# Main_LEDs.net
KiCad netlist of a schematic drawn in Altium Designer
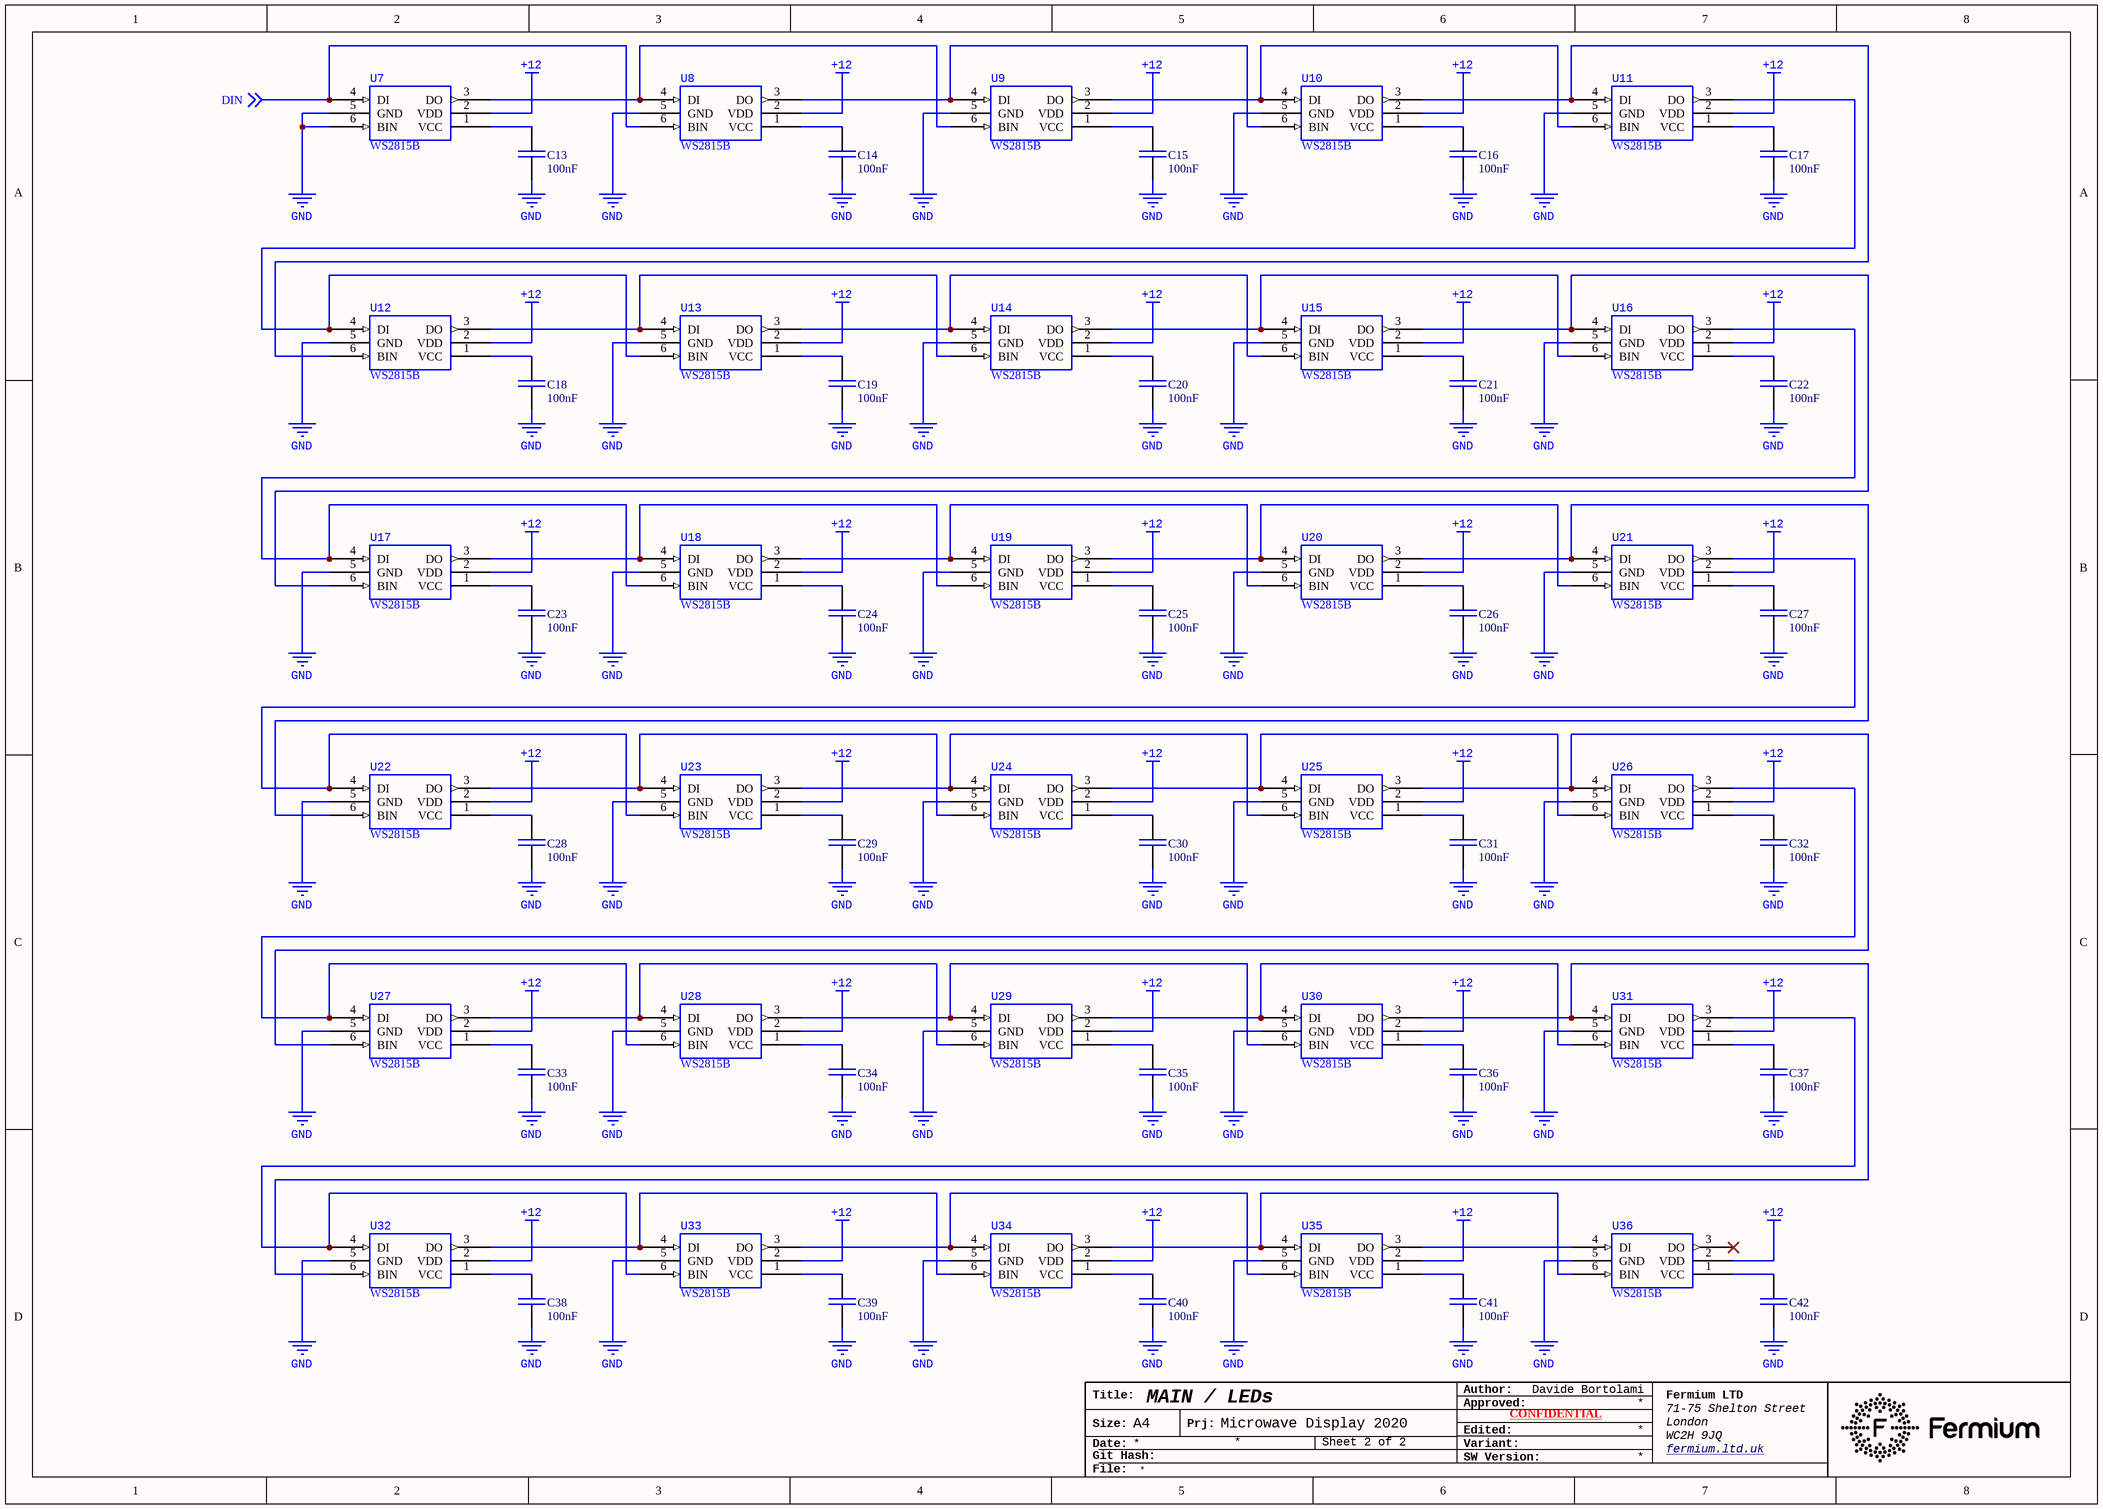
[diagram p0: Main_LEDs.SchDoc]

(export (version "E")
  (design (tool "Eeschema 10.0.6"))
  (components
    (comp (ref "C13")
      (value "100nF")
      (footprint "CAP 0603_1608")
      (description "CAP SMD MLCC 100nF 25V 0603 X7R")
      (fields (field (name "PART NUMBER") "02841f84-ac15-41b5-9e17-915f8f067828"))
      (libsource (lib "frmdblib") (part "GENERIC_C"))
    )
    (comp (ref "C14")
      (value "100nF")
      (footprint "CAP 0603_1608")
      (description "CAP SMD MLCC 100nF 25V 0603 X7R")
      (fields (field (name "PART NUMBER") "02841f84-ac15-41b5-9e17-915f8f067828"))
      (libsource (lib "frmdblib") (part "GENERIC_C"))
    )
    (comp (ref "C15")
      (value "100nF")
      (footprint "CAP 0603_1608")
      (description "CAP SMD MLCC 100nF 25V 0603 X7R")
      (fields (field (name "PART NUMBER") "02841f84-ac15-41b5-9e17-915f8f067828"))
      (libsource (lib "frmdblib") (part "GENERIC_C"))
    )
    (comp (ref "C16")
      (value "100nF")
      (footprint "CAP 0603_1608")
      (description "CAP SMD MLCC 100nF 25V 0603 X7R")
      (fields (field (name "PART NUMBER") "02841f84-ac15-41b5-9e17-915f8f067828"))
      (libsource (lib "frmdblib") (part "GENERIC_C"))
    )
    (comp (ref "C17")
      (value "100nF")
      (footprint "CAP 0603_1608")
      (description "CAP SMD MLCC 100nF 25V 0603 X7R")
      (fields (field (name "PART NUMBER") "02841f84-ac15-41b5-9e17-915f8f067828"))
      (libsource (lib "frmdblib") (part "GENERIC_C"))
    )
    (comp (ref "C18")
      (value "100nF")
      (footprint "CAP 0603_1608")
      (description "CAP SMD MLCC 100nF 25V 0603 X7R")
      (fields (field (name "PART NUMBER") "02841f84-ac15-41b5-9e17-915f8f067828"))
      (libsource (lib "frmdblib") (part "GENERIC_C"))
    )
    (comp (ref "C19")
      (value "100nF")
      (footprint "CAP 0603_1608")
      (description "CAP SMD MLCC 100nF 25V 0603 X7R")
      (fields (field (name "PART NUMBER") "02841f84-ac15-41b5-9e17-915f8f067828"))
      (libsource (lib "frmdblib") (part "GENERIC_C"))
    )
    (comp (ref "C20")
      (value "100nF")
      (footprint "CAP 0603_1608")
      (description "CAP SMD MLCC 100nF 25V 0603 X7R")
      (fields (field (name "PART NUMBER") "02841f84-ac15-41b5-9e17-915f8f067828"))
      (libsource (lib "frmdblib") (part "GENERIC_C"))
    )
    (comp (ref "C21")
      (value "100nF")
      (footprint "CAP 0603_1608")
      (description "CAP SMD MLCC 100nF 25V 0603 X7R")
      (fields (field (name "PART NUMBER") "02841f84-ac15-41b5-9e17-915f8f067828"))
      (libsource (lib "frmdblib") (part "GENERIC_C"))
    )
    (comp (ref "C22")
      (value "100nF")
      (footprint "CAP 0603_1608")
      (description "CAP SMD MLCC 100nF 25V 0603 X7R")
      (fields (field (name "PART NUMBER") "02841f84-ac15-41b5-9e17-915f8f067828"))
      (libsource (lib "frmdblib") (part "GENERIC_C"))
    )
    (comp (ref "C23")
      (value "100nF")
      (footprint "CAP 0603_1608")
      (description "CAP SMD MLCC 100nF 25V 0603 X7R")
      (fields (field (name "PART NUMBER") "02841f84-ac15-41b5-9e17-915f8f067828"))
      (libsource (lib "frmdblib") (part "GENERIC_C"))
    )
    (comp (ref "C24")
      (value "100nF")
      (footprint "CAP 0603_1608")
      (description "CAP SMD MLCC 100nF 25V 0603 X7R")
      (fields (field (name "PART NUMBER") "02841f84-ac15-41b5-9e17-915f8f067828"))
      (libsource (lib "frmdblib") (part "GENERIC_C"))
    )
    (comp (ref "C25")
      (value "100nF")
      (footprint "CAP 0603_1608")
      (description "CAP SMD MLCC 100nF 25V 0603 X7R")
      (fields (field (name "PART NUMBER") "02841f84-ac15-41b5-9e17-915f8f067828"))
      (libsource (lib "frmdblib") (part "GENERIC_C"))
    )
    (comp (ref "C26")
      (value "100nF")
      (footprint "CAP 0603_1608")
      (description "CAP SMD MLCC 100nF 25V 0603 X7R")
      (fields (field (name "PART NUMBER") "02841f84-ac15-41b5-9e17-915f8f067828"))
      (libsource (lib "frmdblib") (part "GENERIC_C"))
    )
    (comp (ref "C27")
      (value "100nF")
      (footprint "CAP 0603_1608")
      (description "CAP SMD MLCC 100nF 25V 0603 X7R")
      (fields (field (name "PART NUMBER") "02841f84-ac15-41b5-9e17-915f8f067828"))
      (libsource (lib "frmdblib") (part "GENERIC_C"))
    )
    (comp (ref "C28")
      (value "100nF")
      (footprint "CAP 0603_1608")
      (description "CAP SMD MLCC 100nF 25V 0603 X7R")
      (fields (field (name "PART NUMBER") "02841f84-ac15-41b5-9e17-915f8f067828"))
      (libsource (lib "frmdblib") (part "GENERIC_C"))
    )
    (comp (ref "C29")
      (value "100nF")
      (footprint "CAP 0603_1608")
      (description "CAP SMD MLCC 100nF 25V 0603 X7R")
      (fields (field (name "PART NUMBER") "02841f84-ac15-41b5-9e17-915f8f067828"))
      (libsource (lib "frmdblib") (part "GENERIC_C"))
    )
    (comp (ref "C30")
      (value "100nF")
      (footprint "CAP 0603_1608")
      (description "CAP SMD MLCC 100nF 25V 0603 X7R")
      (fields (field (name "PART NUMBER") "02841f84-ac15-41b5-9e17-915f8f067828"))
      (libsource (lib "frmdblib") (part "GENERIC_C"))
    )
    (comp (ref "C31")
      (value "100nF")
      (footprint "CAP 0603_1608")
      (description "CAP SMD MLCC 100nF 25V 0603 X7R")
      (fields (field (name "PART NUMBER") "02841f84-ac15-41b5-9e17-915f8f067828"))
      (libsource (lib "frmdblib") (part "GENERIC_C"))
    )
    (comp (ref "C32")
      (value "100nF")
      (footprint "CAP 0603_1608")
      (description "CAP SMD MLCC 100nF 25V 0603 X7R")
      (fields (field (name "PART NUMBER") "02841f84-ac15-41b5-9e17-915f8f067828"))
      (libsource (lib "frmdblib") (part "GENERIC_C"))
    )
    (comp (ref "C33")
      (value "100nF")
      (footprint "CAP 0603_1608")
      (description "CAP SMD MLCC 100nF 25V 0603 X7R")
      (fields (field (name "PART NUMBER") "02841f84-ac15-41b5-9e17-915f8f067828"))
      (libsource (lib "frmdblib") (part "GENERIC_C"))
    )
    (comp (ref "C34")
      (value "100nF")
      (footprint "CAP 0603_1608")
      (description "CAP SMD MLCC 100nF 25V 0603 X7R")
      (fields (field (name "PART NUMBER") "02841f84-ac15-41b5-9e17-915f8f067828"))
      (libsource (lib "frmdblib") (part "GENERIC_C"))
    )
    (comp (ref "C35")
      (value "100nF")
      (footprint "CAP 0603_1608")
      (description "CAP SMD MLCC 100nF 25V 0603 X7R")
      (fields (field (name "PART NUMBER") "02841f84-ac15-41b5-9e17-915f8f067828"))
      (libsource (lib "frmdblib") (part "GENERIC_C"))
    )
    (comp (ref "C36")
      (value "100nF")
      (footprint "CAP 0603_1608")
      (description "CAP SMD MLCC 100nF 25V 0603 X7R")
      (fields (field (name "PART NUMBER") "02841f84-ac15-41b5-9e17-915f8f067828"))
      (libsource (lib "frmdblib") (part "GENERIC_C"))
    )
    (comp (ref "C37")
      (value "100nF")
      (footprint "CAP 0603_1608")
      (description "CAP SMD MLCC 100nF 25V 0603 X7R")
      (fields (field (name "PART NUMBER") "02841f84-ac15-41b5-9e17-915f8f067828"))
      (libsource (lib "frmdblib") (part "GENERIC_C"))
    )
    (comp (ref "C38")
      (value "100nF")
      (footprint "CAP 0603_1608")
      (description "CAP SMD MLCC 100nF 25V 0603 X7R")
      (fields (field (name "PART NUMBER") "02841f84-ac15-41b5-9e17-915f8f067828"))
      (libsource (lib "frmdblib") (part "GENERIC_C"))
    )
    (comp (ref "C39")
      (value "100nF")
      (footprint "CAP 0603_1608")
      (description "CAP SMD MLCC 100nF 25V 0603 X7R")
      (fields (field (name "PART NUMBER") "02841f84-ac15-41b5-9e17-915f8f067828"))
      (libsource (lib "frmdblib") (part "GENERIC_C"))
    )
    (comp (ref "C40")
      (value "100nF")
      (footprint "CAP 0603_1608")
      (description "CAP SMD MLCC 100nF 25V 0603 X7R")
      (fields (field (name "PART NUMBER") "02841f84-ac15-41b5-9e17-915f8f067828"))
      (libsource (lib "frmdblib") (part "GENERIC_C"))
    )
    (comp (ref "C41")
      (value "100nF")
      (footprint "CAP 0603_1608")
      (description "CAP SMD MLCC 100nF 25V 0603 X7R")
      (fields (field (name "PART NUMBER") "02841f84-ac15-41b5-9e17-915f8f067828"))
      (libsource (lib "frmdblib") (part "GENERIC_C"))
    )
    (comp (ref "C42")
      (value "100nF")
      (footprint "CAP 0603_1608")
      (description "CAP SMD MLCC 100nF 25V 0603 X7R")
      (fields (field (name "PART NUMBER") "02841f84-ac15-41b5-9e17-915f8f067828"))
      (libsource (lib "frmdblib") (part "GENERIC_C"))
    )
    (comp (ref "U7")
      (value "WS2815B")
      (footprint "C2100EF9-5A1B-4012-AEAB-289AE8E97B6B")
      (description "IC SMD LED RGB DIGITAL 12V WS2815B")
      (fields (field (name "PART NUMBER") "6f697cdb-93d0-46fc-8e29-f2cd6d395cf4"))
      (libsource (lib "frmdblib") (part "2030838a-96a2-4aaf-b84b-11e32876a490"))
    )
    (comp (ref "U8")
      (value "WS2815B")
      (footprint "C2100EF9-5A1B-4012-AEAB-289AE8E97B6B")
      (description "IC SMD LED RGB DIGITAL 12V WS2815B")
      (fields (field (name "PART NUMBER") "6f697cdb-93d0-46fc-8e29-f2cd6d395cf4"))
      (libsource (lib "frmdblib") (part "2030838a-96a2-4aaf-b84b-11e32876a490"))
    )
    (comp (ref "U9")
      (value "WS2815B")
      (footprint "C2100EF9-5A1B-4012-AEAB-289AE8E97B6B")
      (description "IC SMD LED RGB DIGITAL 12V WS2815B")
      (fields (field (name "PART NUMBER") "6f697cdb-93d0-46fc-8e29-f2cd6d395cf4"))
      (libsource (lib "frmdblib") (part "2030838a-96a2-4aaf-b84b-11e32876a490"))
    )
    (comp (ref "U10")
      (value "WS2815B")
      (footprint "C2100EF9-5A1B-4012-AEAB-289AE8E97B6B")
      (description "IC SMD LED RGB DIGITAL 12V WS2815B")
      (fields (field (name "PART NUMBER") "6f697cdb-93d0-46fc-8e29-f2cd6d395cf4"))
      (libsource (lib "frmdblib") (part "2030838a-96a2-4aaf-b84b-11e32876a490"))
    )
    (comp (ref "U11")
      (value "WS2815B")
      (footprint "C2100EF9-5A1B-4012-AEAB-289AE8E97B6B")
      (description "IC SMD LED RGB DIGITAL 12V WS2815B")
      (fields (field (name "PART NUMBER") "6f697cdb-93d0-46fc-8e29-f2cd6d395cf4"))
      (libsource (lib "frmdblib") (part "2030838a-96a2-4aaf-b84b-11e32876a490"))
    )
    (comp (ref "U12")
      (value "WS2815B")
      (footprint "C2100EF9-5A1B-4012-AEAB-289AE8E97B6B")
      (description "IC SMD LED RGB DIGITAL 12V WS2815B")
      (fields (field (name "PART NUMBER") "6f697cdb-93d0-46fc-8e29-f2cd6d395cf4"))
      (libsource (lib "frmdblib") (part "2030838a-96a2-4aaf-b84b-11e32876a490"))
    )
    (comp (ref "U13")
      (value "WS2815B")
      (footprint "C2100EF9-5A1B-4012-AEAB-289AE8E97B6B")
      (description "IC SMD LED RGB DIGITAL 12V WS2815B")
      (fields (field (name "PART NUMBER") "6f697cdb-93d0-46fc-8e29-f2cd6d395cf4"))
      (libsource (lib "frmdblib") (part "2030838a-96a2-4aaf-b84b-11e32876a490"))
    )
    (comp (ref "U14")
      (value "WS2815B")
      (footprint "C2100EF9-5A1B-4012-AEAB-289AE8E97B6B")
      (description "IC SMD LED RGB DIGITAL 12V WS2815B")
      (fields (field (name "PART NUMBER") "6f697cdb-93d0-46fc-8e29-f2cd6d395cf4"))
      (libsource (lib "frmdblib") (part "2030838a-96a2-4aaf-b84b-11e32876a490"))
    )
    (comp (ref "U15")
      (value "WS2815B")
      (footprint "C2100EF9-5A1B-4012-AEAB-289AE8E97B6B")
      (description "IC SMD LED RGB DIGITAL 12V WS2815B")
      (fields (field (name "PART NUMBER") "6f697cdb-93d0-46fc-8e29-f2cd6d395cf4"))
      (libsource (lib "frmdblib") (part "2030838a-96a2-4aaf-b84b-11e32876a490"))
    )
    (comp (ref "U16")
      (value "WS2815B")
      (footprint "C2100EF9-5A1B-4012-AEAB-289AE8E97B6B")
      (description "IC SMD LED RGB DIGITAL 12V WS2815B")
      (fields (field (name "PART NUMBER") "6f697cdb-93d0-46fc-8e29-f2cd6d395cf4"))
      (libsource (lib "frmdblib") (part "2030838a-96a2-4aaf-b84b-11e32876a490"))
    )
    (comp (ref "U17")
      (value "WS2815B")
      (footprint "C2100EF9-5A1B-4012-AEAB-289AE8E97B6B")
      (description "IC SMD LED RGB DIGITAL 12V WS2815B")
      (fields (field (name "PART NUMBER") "6f697cdb-93d0-46fc-8e29-f2cd6d395cf4"))
      (libsource (lib "frmdblib") (part "2030838a-96a2-4aaf-b84b-11e32876a490"))
    )
    (comp (ref "U18")
      (value "WS2815B")
      (footprint "C2100EF9-5A1B-4012-AEAB-289AE8E97B6B")
      (description "IC SMD LED RGB DIGITAL 12V WS2815B")
      (fields (field (name "PART NUMBER") "6f697cdb-93d0-46fc-8e29-f2cd6d395cf4"))
      (libsource (lib "frmdblib") (part "2030838a-96a2-4aaf-b84b-11e32876a490"))
    )
    (comp (ref "U19")
      (value "WS2815B")
      (footprint "C2100EF9-5A1B-4012-AEAB-289AE8E97B6B")
      (description "IC SMD LED RGB DIGITAL 12V WS2815B")
      (fields (field (name "PART NUMBER") "6f697cdb-93d0-46fc-8e29-f2cd6d395cf4"))
      (libsource (lib "frmdblib") (part "2030838a-96a2-4aaf-b84b-11e32876a490"))
    )
    (comp (ref "U20")
      (value "WS2815B")
      (footprint "C2100EF9-5A1B-4012-AEAB-289AE8E97B6B")
      (description "IC SMD LED RGB DIGITAL 12V WS2815B")
      (fields (field (name "PART NUMBER") "6f697cdb-93d0-46fc-8e29-f2cd6d395cf4"))
      (libsource (lib "frmdblib") (part "2030838a-96a2-4aaf-b84b-11e32876a490"))
    )
    (comp (ref "U21")
      (value "WS2815B")
      (footprint "C2100EF9-5A1B-4012-AEAB-289AE8E97B6B")
      (description "IC SMD LED RGB DIGITAL 12V WS2815B")
      (fields (field (name "PART NUMBER") "6f697cdb-93d0-46fc-8e29-f2cd6d395cf4"))
      (libsource (lib "frmdblib") (part "2030838a-96a2-4aaf-b84b-11e32876a490"))
    )
    (comp (ref "U22")
      (value "WS2815B")
      (footprint "C2100EF9-5A1B-4012-AEAB-289AE8E97B6B")
      (description "IC SMD LED RGB DIGITAL 12V WS2815B")
      (fields (field (name "PART NUMBER") "6f697cdb-93d0-46fc-8e29-f2cd6d395cf4"))
      (libsource (lib "frmdblib") (part "2030838a-96a2-4aaf-b84b-11e32876a490"))
    )
    (comp (ref "U23")
      (value "WS2815B")
      (footprint "C2100EF9-5A1B-4012-AEAB-289AE8E97B6B")
      (description "IC SMD LED RGB DIGITAL 12V WS2815B")
      (fields (field (name "PART NUMBER") "6f697cdb-93d0-46fc-8e29-f2cd6d395cf4"))
      (libsource (lib "frmdblib") (part "2030838a-96a2-4aaf-b84b-11e32876a490"))
    )
    (comp (ref "U24")
      (value "WS2815B")
      (footprint "C2100EF9-5A1B-4012-AEAB-289AE8E97B6B")
      (description "IC SMD LED RGB DIGITAL 12V WS2815B")
      (fields (field (name "PART NUMBER") "6f697cdb-93d0-46fc-8e29-f2cd6d395cf4"))
      (libsource (lib "frmdblib") (part "2030838a-96a2-4aaf-b84b-11e32876a490"))
    )
    (comp (ref "U25")
      (value "WS2815B")
      (footprint "C2100EF9-5A1B-4012-AEAB-289AE8E97B6B")
      (description "IC SMD LED RGB DIGITAL 12V WS2815B")
      (fields (field (name "PART NUMBER") "6f697cdb-93d0-46fc-8e29-f2cd6d395cf4"))
      (libsource (lib "frmdblib") (part "2030838a-96a2-4aaf-b84b-11e32876a490"))
    )
    (comp (ref "U26")
      (value "WS2815B")
      (footprint "C2100EF9-5A1B-4012-AEAB-289AE8E97B6B")
      (description "IC SMD LED RGB DIGITAL 12V WS2815B")
      (fields (field (name "PART NUMBER") "6f697cdb-93d0-46fc-8e29-f2cd6d395cf4"))
      (libsource (lib "frmdblib") (part "2030838a-96a2-4aaf-b84b-11e32876a490"))
    )
    (comp (ref "U27")
      (value "WS2815B")
      (footprint "C2100EF9-5A1B-4012-AEAB-289AE8E97B6B")
      (description "IC SMD LED RGB DIGITAL 12V WS2815B")
      (fields (field (name "PART NUMBER") "6f697cdb-93d0-46fc-8e29-f2cd6d395cf4"))
      (libsource (lib "frmdblib") (part "2030838a-96a2-4aaf-b84b-11e32876a490"))
    )
    (comp (ref "U28")
      (value "WS2815B")
      (footprint "C2100EF9-5A1B-4012-AEAB-289AE8E97B6B")
      (description "IC SMD LED RGB DIGITAL 12V WS2815B")
      (fields (field (name "PART NUMBER") "6f697cdb-93d0-46fc-8e29-f2cd6d395cf4"))
      (libsource (lib "frmdblib") (part "2030838a-96a2-4aaf-b84b-11e32876a490"))
    )
    (comp (ref "U29")
      (value "WS2815B")
      (footprint "C2100EF9-5A1B-4012-AEAB-289AE8E97B6B")
      (description "IC SMD LED RGB DIGITAL 12V WS2815B")
      (fields (field (name "PART NUMBER") "6f697cdb-93d0-46fc-8e29-f2cd6d395cf4"))
      (libsource (lib "frmdblib") (part "2030838a-96a2-4aaf-b84b-11e32876a490"))
    )
    (comp (ref "U30")
      (value "WS2815B")
      (footprint "C2100EF9-5A1B-4012-AEAB-289AE8E97B6B")
      (description "IC SMD LED RGB DIGITAL 12V WS2815B")
      (fields (field (name "PART NUMBER") "6f697cdb-93d0-46fc-8e29-f2cd6d395cf4"))
      (libsource (lib "frmdblib") (part "2030838a-96a2-4aaf-b84b-11e32876a490"))
    )
    (comp (ref "U31")
      (value "WS2815B")
      (footprint "C2100EF9-5A1B-4012-AEAB-289AE8E97B6B")
      (description "IC SMD LED RGB DIGITAL 12V WS2815B")
      (fields (field (name "PART NUMBER") "6f697cdb-93d0-46fc-8e29-f2cd6d395cf4"))
      (libsource (lib "frmdblib") (part "2030838a-96a2-4aaf-b84b-11e32876a490"))
    )
    (comp (ref "U32")
      (value "WS2815B")
      (footprint "C2100EF9-5A1B-4012-AEAB-289AE8E97B6B")
      (description "IC SMD LED RGB DIGITAL 12V WS2815B")
      (fields (field (name "PART NUMBER") "6f697cdb-93d0-46fc-8e29-f2cd6d395cf4"))
      (libsource (lib "frmdblib") (part "2030838a-96a2-4aaf-b84b-11e32876a490"))
    )
    (comp (ref "U33")
      (value "WS2815B")
      (footprint "C2100EF9-5A1B-4012-AEAB-289AE8E97B6B")
      (description "IC SMD LED RGB DIGITAL 12V WS2815B")
      (fields (field (name "PART NUMBER") "6f697cdb-93d0-46fc-8e29-f2cd6d395cf4"))
      (libsource (lib "frmdblib") (part "2030838a-96a2-4aaf-b84b-11e32876a490"))
    )
    (comp (ref "U34")
      (value "WS2815B")
      (footprint "C2100EF9-5A1B-4012-AEAB-289AE8E97B6B")
      (description "IC SMD LED RGB DIGITAL 12V WS2815B")
      (fields (field (name "PART NUMBER") "6f697cdb-93d0-46fc-8e29-f2cd6d395cf4"))
      (libsource (lib "frmdblib") (part "2030838a-96a2-4aaf-b84b-11e32876a490"))
    )
    (comp (ref "U35")
      (value "WS2815B")
      (footprint "C2100EF9-5A1B-4012-AEAB-289AE8E97B6B")
      (description "IC SMD LED RGB DIGITAL 12V WS2815B")
      (fields (field (name "PART NUMBER") "6f697cdb-93d0-46fc-8e29-f2cd6d395cf4"))
      (libsource (lib "frmdblib") (part "2030838a-96a2-4aaf-b84b-11e32876a490"))
    )
    (comp (ref "U36")
      (value "WS2815B")
      (footprint "C2100EF9-5A1B-4012-AEAB-289AE8E97B6B")
      (description "IC SMD LED RGB DIGITAL 12V WS2815B")
      (fields (field (name "PART NUMBER") "6f697cdb-93d0-46fc-8e29-f2cd6d395cf4"))
      (libsource (lib "frmdblib") (part "2030838a-96a2-4aaf-b84b-11e32876a490"))
    )
  )
  (nets
    (net (code "1") (name "+12") (class "Default")
      (node (ref "U10") (pin "2") (pinfunction "VDD_2") (pintype "power_in"))
      (node (ref "U11") (pin "2") (pinfunction "VDD_2") (pintype "power_in"))
      (node (ref "U12") (pin "2") (pinfunction "VDD_2") (pintype "power_in"))
      (node (ref "U13") (pin "2") (pinfunction "VDD_2") (pintype "power_in"))
      (node (ref "U14") (pin "2") (pinfunction "VDD_2") (pintype "power_in"))
      (node (ref "U15") (pin "2") (pinfunction "VDD_2") (pintype "power_in"))
      (node (ref "U16") (pin "2") (pinfunction "VDD_2") (pintype "power_in"))
      (node (ref "U17") (pin "2") (pinfunction "VDD_2") (pintype "power_in"))
      (node (ref "U18") (pin "2") (pinfunction "VDD_2") (pintype "power_in"))
      (node (ref "U19") (pin "2") (pinfunction "VDD_2") (pintype "power_in"))
      (node (ref "U20") (pin "2") (pinfunction "VDD_2") (pintype "power_in"))
      (node (ref "U21") (pin "2") (pinfunction "VDD_2") (pintype "power_in"))
      (node (ref "U22") (pin "2") (pinfunction "VDD_2") (pintype "power_in"))
      (node (ref "U23") (pin "2") (pinfunction "VDD_2") (pintype "power_in"))
      (node (ref "U24") (pin "2") (pinfunction "VDD_2") (pintype "power_in"))
      (node (ref "U25") (pin "2") (pinfunction "VDD_2") (pintype "power_in"))
      (node (ref "U26") (pin "2") (pinfunction "VDD_2") (pintype "power_in"))
      (node (ref "U27") (pin "2") (pinfunction "VDD_2") (pintype "power_in"))
      (node (ref "U28") (pin "2") (pinfunction "VDD_2") (pintype "power_in"))
      (node (ref "U29") (pin "2") (pinfunction "VDD_2") (pintype "power_in"))
      (node (ref "U30") (pin "2") (pinfunction "VDD_2") (pintype "power_in"))
      (node (ref "U31") (pin "2") (pinfunction "VDD_2") (pintype "power_in"))
      (node (ref "U32") (pin "2") (pinfunction "VDD_2") (pintype "power_in"))
      (node (ref "U33") (pin "2") (pinfunction "VDD_2") (pintype "power_in"))
      (node (ref "U34") (pin "2") (pinfunction "VDD_2") (pintype "power_in"))
      (node (ref "U35") (pin "2") (pinfunction "VDD_2") (pintype "power_in"))
      (node (ref "U36") (pin "2") (pinfunction "VDD_2") (pintype "power_in"))
      (node (ref "U7") (pin "2") (pinfunction "VDD_2") (pintype "power_in"))
      (node (ref "U8") (pin "2") (pinfunction "VDD_2") (pintype "power_in"))
      (node (ref "U9") (pin "2") (pinfunction "VDD_2") (pintype "power_in"))
    )
    (net (code "2") (name "DIN") (class "Default")
      (node (ref "U7") (pin "4") (pinfunction "DI_4") (pintype "input"))
      (node (ref "U8") (pin "6") (pinfunction "BIN_6") (pintype "input"))
    )
    (net (code "3") (name "GND") (class "Default")
      (node (ref "C13") (pin "2") (pintype "passive"))
      (node (ref "C14") (pin "2") (pintype "passive"))
      (node (ref "C15") (pin "2") (pintype "passive"))
      (node (ref "C16") (pin "2") (pintype "passive"))
      (node (ref "C17") (pin "2") (pintype "passive"))
      (node (ref "C18") (pin "2") (pintype "passive"))
      (node (ref "C19") (pin "2") (pintype "passive"))
      (node (ref "C20") (pin "2") (pintype "passive"))
      (node (ref "C21") (pin "2") (pintype "passive"))
      (node (ref "C22") (pin "2") (pintype "passive"))
      (node (ref "C23") (pin "2") (pintype "passive"))
      (node (ref "C24") (pin "2") (pintype "passive"))
      (node (ref "C25") (pin "2") (pintype "passive"))
      (node (ref "C26") (pin "2") (pintype "passive"))
      (node (ref "C27") (pin "2") (pintype "passive"))
      (node (ref "C28") (pin "2") (pintype "passive"))
      (node (ref "C29") (pin "2") (pintype "passive"))
      (node (ref "C30") (pin "2") (pintype "passive"))
      (node (ref "C31") (pin "2") (pintype "passive"))
      (node (ref "C32") (pin "2") (pintype "passive"))
      (node (ref "C33") (pin "2") (pintype "passive"))
      (node (ref "C34") (pin "2") (pintype "passive"))
      (node (ref "C35") (pin "2") (pintype "passive"))
      (node (ref "C36") (pin "2") (pintype "passive"))
      (node (ref "C37") (pin "2") (pintype "passive"))
      (node (ref "C38") (pin "2") (pintype "passive"))
      (node (ref "C39") (pin "2") (pintype "passive"))
      (node (ref "C40") (pin "2") (pintype "passive"))
      (node (ref "C41") (pin "2") (pintype "passive"))
      (node (ref "C42") (pin "2") (pintype "passive"))
      (node (ref "U10") (pin "5") (pinfunction "GND_5") (pintype "power_in"))
      (node (ref "U11") (pin "5") (pinfunction "GND_5") (pintype "power_in"))
      (node (ref "U12") (pin "5") (pinfunction "GND_5") (pintype "power_in"))
      (node (ref "U13") (pin "5") (pinfunction "GND_5") (pintype "power_in"))
      (node (ref "U14") (pin "5") (pinfunction "GND_5") (pintype "power_in"))
      (node (ref "U15") (pin "5") (pinfunction "GND_5") (pintype "power_in"))
      (node (ref "U16") (pin "5") (pinfunction "GND_5") (pintype "power_in"))
      (node (ref "U17") (pin "5") (pinfunction "GND_5") (pintype "power_in"))
      (node (ref "U18") (pin "5") (pinfunction "GND_5") (pintype "power_in"))
      (node (ref "U19") (pin "5") (pinfunction "GND_5") (pintype "power_in"))
      (node (ref "U20") (pin "5") (pinfunction "GND_5") (pintype "power_in"))
      (node (ref "U21") (pin "5") (pinfunction "GND_5") (pintype "power_in"))
      (node (ref "U22") (pin "5") (pinfunction "GND_5") (pintype "power_in"))
      (node (ref "U23") (pin "5") (pinfunction "GND_5") (pintype "power_in"))
      (node (ref "U24") (pin "5") (pinfunction "GND_5") (pintype "power_in"))
      (node (ref "U25") (pin "5") (pinfunction "GND_5") (pintype "power_in"))
      (node (ref "U26") (pin "5") (pinfunction "GND_5") (pintype "power_in"))
      (node (ref "U27") (pin "5") (pinfunction "GND_5") (pintype "power_in"))
      (node (ref "U28") (pin "5") (pinfunction "GND_5") (pintype "power_in"))
      (node (ref "U29") (pin "5") (pinfunction "GND_5") (pintype "power_in"))
      (node (ref "U30") (pin "5") (pinfunction "GND_5") (pintype "power_in"))
      (node (ref "U31") (pin "5") (pinfunction "GND_5") (pintype "power_in"))
      (node (ref "U32") (pin "5") (pinfunction "GND_5") (pintype "power_in"))
      (node (ref "U33") (pin "5") (pinfunction "GND_5") (pintype "power_in"))
      (node (ref "U34") (pin "5") (pinfunction "GND_5") (pintype "power_in"))
      (node (ref "U35") (pin "5") (pinfunction "GND_5") (pintype "power_in"))
      (node (ref "U36") (pin "5") (pinfunction "GND_5") (pintype "power_in"))
      (node (ref "U7") (pin "5") (pinfunction "GND_5") (pintype "power_in"))
      (node (ref "U7") (pin "6") (pinfunction "BIN_6") (pintype "input"))
      (node (ref "U8") (pin "5") (pinfunction "GND_5") (pintype "power_in"))
      (node (ref "U9") (pin "5") (pinfunction "GND_5") (pintype "power_in"))
    )
    (net (code "4") (name "Net-(U7-DO)") (class "Default")
      (node (ref "U7") (pin "3") (pinfunction "DO_3") (pintype "output"))
      (node (ref "U8") (pin "4") (pinfunction "DI_4") (pintype "input"))
      (node (ref "U9") (pin "6") (pinfunction "BIN_6") (pintype "input"))
    )
    (net (code "5") (name "Net-(U7-VCC)") (class "Default")
      (node (ref "C13") (pin "1") (pintype "passive"))
      (node (ref "U7") (pin "1") (pinfunction "VCC_1") (pintype "power_in"))
    )
    (net (code "6") (name "Net-(U8-VCC)") (class "Default")
      (node (ref "C14") (pin "1") (pintype "passive"))
      (node (ref "U8") (pin "1") (pinfunction "VCC_1") (pintype "power_in"))
    )
    (net (code "7") (name "Net-(U9-VCC)") (class "Default")
      (node (ref "C15") (pin "1") (pintype "passive"))
      (node (ref "U9") (pin "1") (pinfunction "VCC_1") (pintype "power_in"))
    )
    (net (code "8") (name "Net-(U10-BIN)") (class "Default")
      (node (ref "U10") (pin "6") (pinfunction "BIN_6") (pintype "input"))
      (node (ref "U8") (pin "3") (pinfunction "DO_3") (pintype "output"))
      (node (ref "U9") (pin "4") (pinfunction "DI_4") (pintype "input"))
    )
    (net (code "9") (name "Net-(U10-DI)") (class "Default")
      (node (ref "U10") (pin "4") (pinfunction "DI_4") (pintype "input"))
      (node (ref "U11") (pin "6") (pinfunction "BIN_6") (pintype "input"))
      (node (ref "U9") (pin "3") (pinfunction "DO_3") (pintype "output"))
    )
    (net (code "10") (name "Net-(U10-DO)") (class "Default")
      (node (ref "U10") (pin "3") (pinfunction "DO_3") (pintype "output"))
      (node (ref "U11") (pin "4") (pinfunction "DI_4") (pintype "input"))
      (node (ref "U12") (pin "6") (pinfunction "BIN_6") (pintype "input"))
    )
    (net (code "11") (name "Net-(U10-VCC)") (class "Default")
      (node (ref "C16") (pin "1") (pintype "passive"))
      (node (ref "U10") (pin "1") (pinfunction "VCC_1") (pintype "power_in"))
    )
    (net (code "12") (name "Net-(U11-DO)") (class "Default")
      (node (ref "U11") (pin "3") (pinfunction "DO_3") (pintype "output"))
      (node (ref "U12") (pin "4") (pinfunction "DI_4") (pintype "input"))
      (node (ref "U13") (pin "6") (pinfunction "BIN_6") (pintype "input"))
    )
    (net (code "13") (name "Net-(U11-VCC)") (class "Default")
      (node (ref "C17") (pin "1") (pintype "passive"))
      (node (ref "U11") (pin "1") (pinfunction "VCC_1") (pintype "power_in"))
    )
    (net (code "14") (name "Net-(U12-DO)") (class "Default")
      (node (ref "U12") (pin "3") (pinfunction "DO_3") (pintype "output"))
      (node (ref "U13") (pin "4") (pinfunction "DI_4") (pintype "input"))
      (node (ref "U14") (pin "6") (pinfunction "BIN_6") (pintype "input"))
    )
    (net (code "15") (name "Net-(U12-VCC)") (class "Default")
      (node (ref "C18") (pin "1") (pintype "passive"))
      (node (ref "U12") (pin "1") (pinfunction "VCC_1") (pintype "power_in"))
    )
    (net (code "16") (name "Net-(U13-DO)") (class "Default")
      (node (ref "U13") (pin "3") (pinfunction "DO_3") (pintype "output"))
      (node (ref "U14") (pin "4") (pinfunction "DI_4") (pintype "input"))
      (node (ref "U15") (pin "6") (pinfunction "BIN_6") (pintype "input"))
    )
    (net (code "17") (name "Net-(U13-VCC)") (class "Default")
      (node (ref "C19") (pin "1") (pintype "passive"))
      (node (ref "U13") (pin "1") (pinfunction "VCC_1") (pintype "power_in"))
    )
    (net (code "18") (name "Net-(U14-DO)") (class "Default")
      (node (ref "U14") (pin "3") (pinfunction "DO_3") (pintype "output"))
      (node (ref "U15") (pin "4") (pinfunction "DI_4") (pintype "input"))
      (node (ref "U16") (pin "6") (pinfunction "BIN_6") (pintype "input"))
    )
    (net (code "19") (name "Net-(U14-VCC)") (class "Default")
      (node (ref "C20") (pin "1") (pintype "passive"))
      (node (ref "U14") (pin "1") (pinfunction "VCC_1") (pintype "power_in"))
    )
    (net (code "20") (name "Net-(U15-DO)") (class "Default")
      (node (ref "U15") (pin "3") (pinfunction "DO_3") (pintype "output"))
      (node (ref "U16") (pin "4") (pinfunction "DI_4") (pintype "input"))
      (node (ref "U17") (pin "6") (pinfunction "BIN_6") (pintype "input"))
    )
    (net (code "21") (name "Net-(U15-VCC)") (class "Default")
      (node (ref "C21") (pin "1") (pintype "passive"))
      (node (ref "U15") (pin "1") (pinfunction "VCC_1") (pintype "power_in"))
    )
    (net (code "22") (name "Net-(U16-DO)") (class "Default")
      (node (ref "U16") (pin "3") (pinfunction "DO_3") (pintype "output"))
      (node (ref "U17") (pin "4") (pinfunction "DI_4") (pintype "input"))
      (node (ref "U18") (pin "6") (pinfunction "BIN_6") (pintype "input"))
    )
    (net (code "23") (name "Net-(U16-VCC)") (class "Default")
      (node (ref "C22") (pin "1") (pintype "passive"))
      (node (ref "U16") (pin "1") (pinfunction "VCC_1") (pintype "power_in"))
    )
    (net (code "24") (name "Net-(U17-DO)") (class "Default")
      (node (ref "U17") (pin "3") (pinfunction "DO_3") (pintype "output"))
      (node (ref "U18") (pin "4") (pinfunction "DI_4") (pintype "input"))
      (node (ref "U19") (pin "6") (pinfunction "BIN_6") (pintype "input"))
    )
    (net (code "25") (name "Net-(U17-VCC)") (class "Default")
      (node (ref "C23") (pin "1") (pintype "passive"))
      (node (ref "U17") (pin "1") (pinfunction "VCC_1") (pintype "power_in"))
    )
    (net (code "26") (name "Net-(U18-DO)") (class "Default")
      (node (ref "U18") (pin "3") (pinfunction "DO_3") (pintype "output"))
      (node (ref "U19") (pin "4") (pinfunction "DI_4") (pintype "input"))
      (node (ref "U20") (pin "6") (pinfunction "BIN_6") (pintype "input"))
    )
    (net (code "27") (name "Net-(U18-VCC)") (class "Default")
      (node (ref "C24") (pin "1") (pintype "passive"))
      (node (ref "U18") (pin "1") (pinfunction "VCC_1") (pintype "power_in"))
    )
    (net (code "28") (name "Net-(U19-DO)") (class "Default")
      (node (ref "U19") (pin "3") (pinfunction "DO_3") (pintype "output"))
      (node (ref "U20") (pin "4") (pinfunction "DI_4") (pintype "input"))
      (node (ref "U21") (pin "6") (pinfunction "BIN_6") (pintype "input"))
    )
    (net (code "29") (name "Net-(U19-VCC)") (class "Default")
      (node (ref "C25") (pin "1") (pintype "passive"))
      (node (ref "U19") (pin "1") (pinfunction "VCC_1") (pintype "power_in"))
    )
    (net (code "30") (name "Net-(U20-DO)") (class "Default")
      (node (ref "U20") (pin "3") (pinfunction "DO_3") (pintype "output"))
      (node (ref "U21") (pin "4") (pinfunction "DI_4") (pintype "input"))
      (node (ref "U22") (pin "6") (pinfunction "BIN_6") (pintype "input"))
    )
    (net (code "31") (name "Net-(U20-VCC)") (class "Default")
      (node (ref "C26") (pin "1") (pintype "passive"))
      (node (ref "U20") (pin "1") (pinfunction "VCC_1") (pintype "power_in"))
    )
    (net (code "32") (name "Net-(U21-DO)") (class "Default")
      (node (ref "U21") (pin "3") (pinfunction "DO_3") (pintype "output"))
      (node (ref "U22") (pin "4") (pinfunction "DI_4") (pintype "input"))
      (node (ref "U23") (pin "6") (pinfunction "BIN_6") (pintype "input"))
    )
    (net (code "33") (name "Net-(U21-VCC)") (class "Default")
      (node (ref "C27") (pin "1") (pintype "passive"))
      (node (ref "U21") (pin "1") (pinfunction "VCC_1") (pintype "power_in"))
    )
    (net (code "34") (name "Net-(U22-DO)") (class "Default")
      (node (ref "U22") (pin "3") (pinfunction "DO_3") (pintype "output"))
      (node (ref "U23") (pin "4") (pinfunction "DI_4") (pintype "input"))
      (node (ref "U24") (pin "6") (pinfunction "BIN_6") (pintype "input"))
    )
    (net (code "35") (name "Net-(U22-VCC)") (class "Default")
      (node (ref "C28") (pin "1") (pintype "passive"))
      (node (ref "U22") (pin "1") (pinfunction "VCC_1") (pintype "power_in"))
    )
    (net (code "36") (name "Net-(U23-DO)") (class "Default")
      (node (ref "U23") (pin "3") (pinfunction "DO_3") (pintype "output"))
      (node (ref "U24") (pin "4") (pinfunction "DI_4") (pintype "input"))
      (node (ref "U25") (pin "6") (pinfunction "BIN_6") (pintype "input"))
    )
    (net (code "37") (name "Net-(U23-VCC)") (class "Default")
      (node (ref "C29") (pin "1") (pintype "passive"))
      (node (ref "U23") (pin "1") (pinfunction "VCC_1") (pintype "power_in"))
    )
    (net (code "38") (name "Net-(U24-DO)") (class "Default")
      (node (ref "U24") (pin "3") (pinfunction "DO_3") (pintype "output"))
      (node (ref "U25") (pin "4") (pinfunction "DI_4") (pintype "input"))
      (node (ref "U26") (pin "6") (pinfunction "BIN_6") (pintype "input"))
    )
    (net (code "39") (name "Net-(U24-VCC)") (class "Default")
      (node (ref "C30") (pin "1") (pintype "passive"))
      (node (ref "U24") (pin "1") (pinfunction "VCC_1") (pintype "power_in"))
    )
    (net (code "40") (name "Net-(U25-DO)") (class "Default")
      (node (ref "U25") (pin "3") (pinfunction "DO_3") (pintype "output"))
      (node (ref "U26") (pin "4") (pinfunction "DI_4") (pintype "input"))
      (node (ref "U27") (pin "6") (pinfunction "BIN_6") (pintype "input"))
    )
    (net (code "41") (name "Net-(U25-VCC)") (class "Default")
      (node (ref "C31") (pin "1") (pintype "passive"))
      (node (ref "U25") (pin "1") (pinfunction "VCC_1") (pintype "power_in"))
    )
    (net (code "42") (name "Net-(U26-DO)") (class "Default")
      (node (ref "U26") (pin "3") (pinfunction "DO_3") (pintype "output"))
      (node (ref "U27") (pin "4") (pinfunction "DI_4") (pintype "input"))
      (node (ref "U28") (pin "6") (pinfunction "BIN_6") (pintype "input"))
    )
    (net (code "43") (name "Net-(U26-VCC)") (class "Default")
      (node (ref "C32") (pin "1") (pintype "passive"))
      (node (ref "U26") (pin "1") (pinfunction "VCC_1") (pintype "power_in"))
    )
    (net (code "44") (name "Net-(U27-DO)") (class "Default")
      (node (ref "U27") (pin "3") (pinfunction "DO_3") (pintype "output"))
      (node (ref "U28") (pin "4") (pinfunction "DI_4") (pintype "input"))
      (node (ref "U29") (pin "6") (pinfunction "BIN_6") (pintype "input"))
    )
    (net (code "45") (name "Net-(U27-VCC)") (class "Default")
      (node (ref "C33") (pin "1") (pintype "passive"))
      (node (ref "U27") (pin "1") (pinfunction "VCC_1") (pintype "power_in"))
    )
    (net (code "46") (name "Net-(U28-DO)") (class "Default")
      (node (ref "U28") (pin "3") (pinfunction "DO_3") (pintype "output"))
      (node (ref "U29") (pin "4") (pinfunction "DI_4") (pintype "input"))
      (node (ref "U30") (pin "6") (pinfunction "BIN_6") (pintype "input"))
    )
    (net (code "47") (name "Net-(U28-VCC)") (class "Default")
      (node (ref "C34") (pin "1") (pintype "passive"))
      (node (ref "U28") (pin "1") (pinfunction "VCC_1") (pintype "power_in"))
    )
    (net (code "48") (name "Net-(U29-DO)") (class "Default")
      (node (ref "U29") (pin "3") (pinfunction "DO_3") (pintype "output"))
      (node (ref "U30") (pin "4") (pinfunction "DI_4") (pintype "input"))
      (node (ref "U31") (pin "6") (pinfunction "BIN_6") (pintype "input"))
    )
    (net (code "49") (name "Net-(U29-VCC)") (class "Default")
      (node (ref "C35") (pin "1") (pintype "passive"))
      (node (ref "U29") (pin "1") (pinfunction "VCC_1") (pintype "power_in"))
    )
    (net (code "50") (name "Net-(U30-DO)") (class "Default")
      (node (ref "U30") (pin "3") (pinfunction "DO_3") (pintype "output"))
      (node (ref "U31") (pin "4") (pinfunction "DI_4") (pintype "input"))
      (node (ref "U32") (pin "6") (pinfunction "BIN_6") (pintype "input"))
    )
    (net (code "51") (name "Net-(U30-VCC)") (class "Default")
      (node (ref "C36") (pin "1") (pintype "passive"))
      (node (ref "U30") (pin "1") (pinfunction "VCC_1") (pintype "power_in"))
    )
    (net (code "52") (name "Net-(U31-DO)") (class "Default")
      (node (ref "U31") (pin "3") (pinfunction "DO_3") (pintype "output"))
      (node (ref "U32") (pin "4") (pinfunction "DI_4") (pintype "input"))
      (node (ref "U33") (pin "6") (pinfunction "BIN_6") (pintype "input"))
    )
    (net (code "53") (name "Net-(U31-VCC)") (class "Default")
      (node (ref "C37") (pin "1") (pintype "passive"))
      (node (ref "U31") (pin "1") (pinfunction "VCC_1") (pintype "power_in"))
    )
    (net (code "54") (name "Net-(U32-DO)") (class "Default")
      (node (ref "U32") (pin "3") (pinfunction "DO_3") (pintype "output"))
      (node (ref "U33") (pin "4") (pinfunction "DI_4") (pintype "input"))
      (node (ref "U34") (pin "6") (pinfunction "BIN_6") (pintype "input"))
    )
    (net (code "55") (name "Net-(U32-VCC)") (class "Default")
      (node (ref "C38") (pin "1") (pintype "passive"))
      (node (ref "U32") (pin "1") (pinfunction "VCC_1") (pintype "power_in"))
    )
    (net (code "56") (name "Net-(U33-DO)") (class "Default")
      (node (ref "U33") (pin "3") (pinfunction "DO_3") (pintype "output"))
      (node (ref "U34") (pin "4") (pinfunction "DI_4") (pintype "input"))
      (node (ref "U35") (pin "6") (pinfunction "BIN_6") (pintype "input"))
    )
    (net (code "57") (name "Net-(U33-VCC)") (class "Default")
      (node (ref "C39") (pin "1") (pintype "passive"))
      (node (ref "U33") (pin "1") (pinfunction "VCC_1") (pintype "power_in"))
    )
    (net (code "58") (name "Net-(U34-DO)") (class "Default")
      (node (ref "U34") (pin "3") (pinfunction "DO_3") (pintype "output"))
      (node (ref "U35") (pin "4") (pinfunction "DI_4") (pintype "input"))
      (node (ref "U36") (pin "6") (pinfunction "BIN_6") (pintype "input"))
    )
    (net (code "59") (name "Net-(U34-VCC)") (class "Default")
      (node (ref "C40") (pin "1") (pintype "passive"))
      (node (ref "U34") (pin "1") (pinfunction "VCC_1") (pintype "power_in"))
    )
    (net (code "60") (name "Net-(U35-DO)") (class "Default")
      (node (ref "U35") (pin "3") (pinfunction "DO_3") (pintype "output"))
      (node (ref "U36") (pin "4") (pinfunction "DI_4") (pintype "input"))
    )
    (net (code "61") (name "Net-(U35-VCC)") (class "Default")
      (node (ref "C41") (pin "1") (pintype "passive"))
      (node (ref "U35") (pin "1") (pinfunction "VCC_1") (pintype "power_in"))
    )
    (net (code "62") (name "Net-(U36-VCC)") (class "Default")
      (node (ref "C42") (pin "1") (pintype "passive"))
      (node (ref "U36") (pin "1") (pinfunction "VCC_1") (pintype "power_in"))
    )
    (net (code "63") (name "unconnected-(U36-DO-Pad3)") (class "Default")
      (node (ref "U36") (pin "3") (pinfunction "DO_3") (pintype "output+no_connect"))
    )
  )
)
